# HoneyPI_Platine_2_0.net
KiCad netlist of a schematic drawn in EAGLE
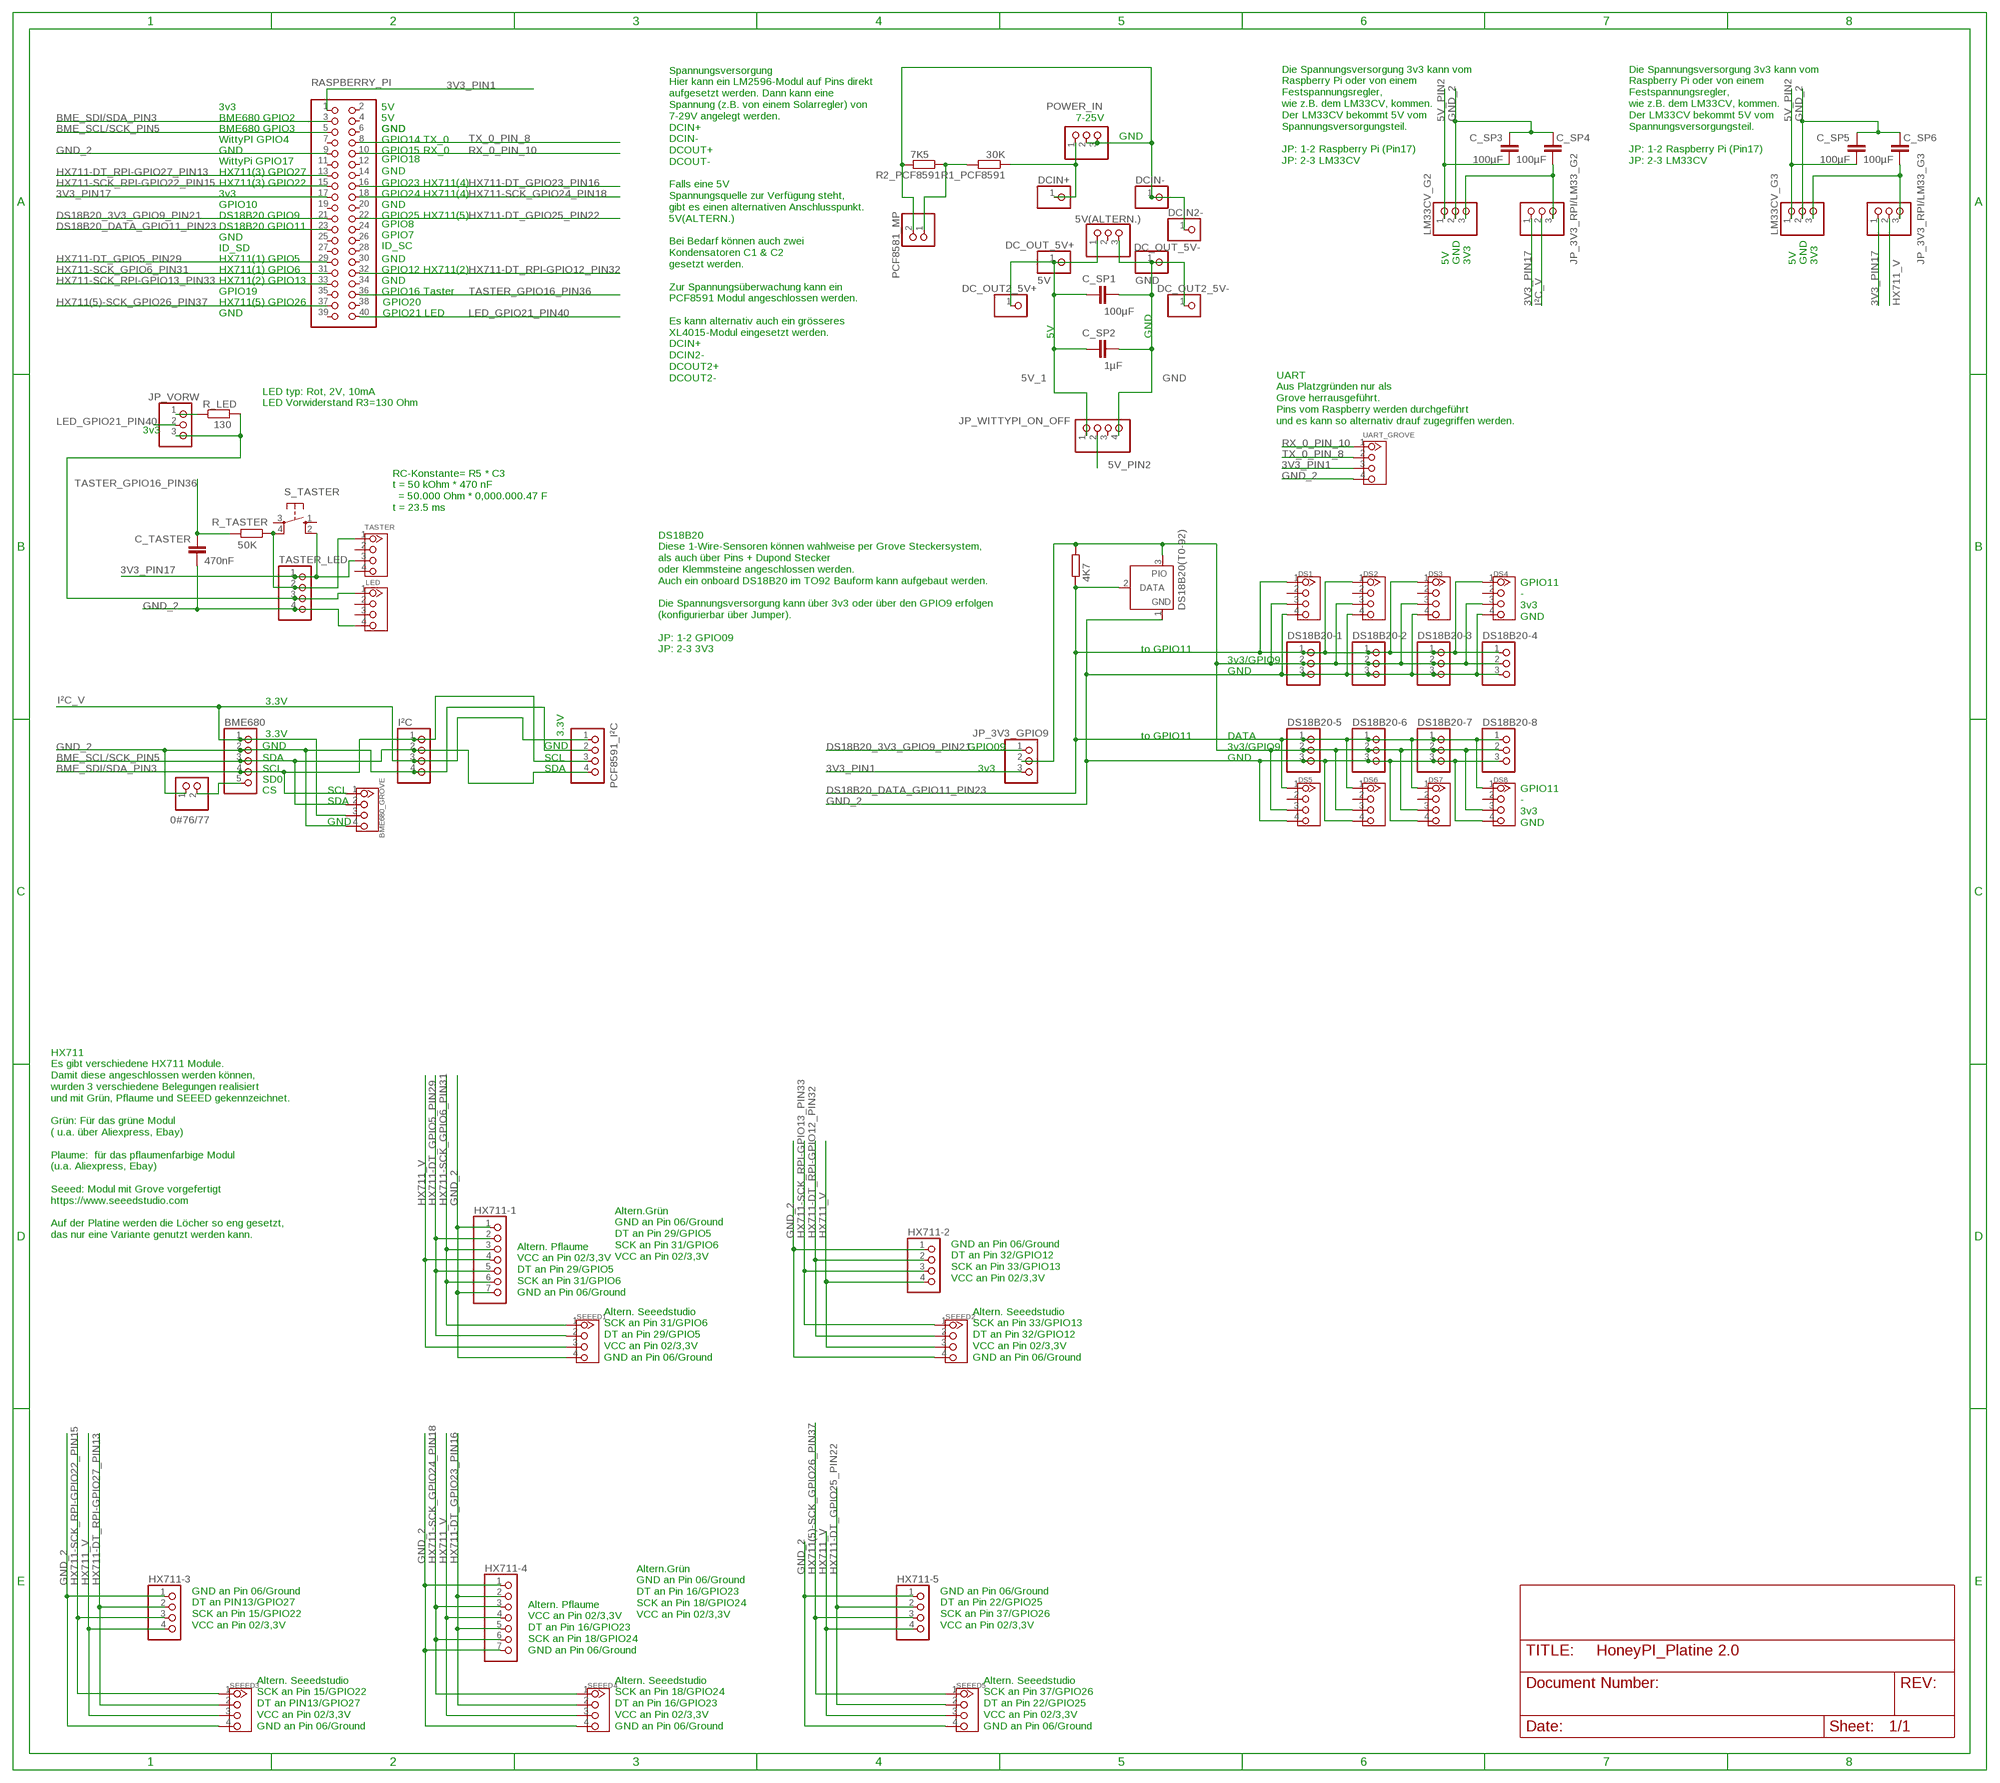
[diagram p0: schematic, sheet 1]

(export (version "E")
  (design (tool "Eeschema 10.0.6"))
  (components
    (comp (ref "0#76/77")
      (value "PINHD-1X2")
      (footprint "eagle-import:1X02")
      (libsource (lib "eagle-import") (part "PINHD-1X2"))
    )
    (comp (ref "5V(ALTERN.)")
      (value "PINHD-1X3")
      (footprint "eagle-import:1X03")
      (libsource (lib "eagle-import") (part "PINHD-1X3"))
    )
    (comp (ref "BME680")
      (value "PINHD-1X5")
      (footprint "eagle-import:1X05")
      (libsource (lib "eagle-import") (part "PINHD-1X5"))
    )
    (comp (ref "BME680_GROVE")
      (value "TWIG-4P-2.0-2.0")
      (footprint "eagle-import:4P-2.0")
      (libsource (lib "eagle-import") (part "TWIG-4P-2.0-2.0"))
    )
    (comp (ref "C_SP1")
      (value "100µF")
      (footprint "eagle-import:C2.5-3")
      (libsource (lib "eagle-import") (part "C2,5-3"))
    )
    (comp (ref "C_SP2")
      (value "1µF")
      (footprint "eagle-import:C2.5-3")
      (libsource (lib "eagle-import") (part "C2,5-3"))
    )
    (comp (ref "C_SP3")
      (value "100µF")
      (footprint "eagle-import:C2.5-3")
      (libsource (lib "eagle-import") (part "C2,5-3"))
    )
    (comp (ref "C_SP4")
      (value "100µF")
      (footprint "eagle-import:C2.5-3")
      (libsource (lib "eagle-import") (part "C2,5-3"))
    )
    (comp (ref "C_SP5")
      (value "100µF")
      (footprint "eagle-import:C2.5-3")
      (libsource (lib "eagle-import") (part "C2,5-3"))
    )
    (comp (ref "C_SP6")
      (value "100µF")
      (footprint "eagle-import:C2.5-3")
      (libsource (lib "eagle-import") (part "C2,5-3"))
    )
    (comp (ref "C_TASTER")
      (value "470nF")
      (footprint "eagle-import:C2.5-3")
      (libsource (lib "eagle-import") (part "C2,5-3"))
    )
    (comp (ref "DCIN+")
      (value "PINHD-1X1")
      (footprint "eagle-import:1X01")
      (libsource (lib "eagle-import") (part "PINHD-1X1"))
    )
    (comp (ref "DCIN-")
      (value "PINHD-1X1")
      (footprint "eagle-import:1X01")
      (libsource (lib "eagle-import") (part "PINHD-1X1"))
    )
    (comp (ref "DCIN2-")
      (value "PINHD-1X1")
      (footprint "eagle-import:1X01")
      (libsource (lib "eagle-import") (part "PINHD-1X1"))
    )
    (comp (ref "DC_OUT2_5V+")
      (value "PINHD-1X1")
      (footprint "eagle-import:1X01")
      (libsource (lib "eagle-import") (part "PINHD-1X1"))
    )
    (comp (ref "DC_OUT2_5V-")
      (value "PINHD-1X1")
      (footprint "eagle-import:1X01")
      (libsource (lib "eagle-import") (part "PINHD-1X1"))
    )
    (comp (ref "DC_OUT_5V+")
      (value "5V")
      (footprint "eagle-import:1X01")
      (libsource (lib "eagle-import") (part "PINHD-1X1"))
    )
    (comp (ref "DC_OUT_5V-")
      (value "GND")
      (footprint "eagle-import:1X01")
      (libsource (lib "eagle-import") (part "PINHD-1X1"))
    )
    (comp (ref "DS1")
      (value "TWIG-4P-2.0-2.0")
      (footprint "eagle-import:4P-2.0")
      (libsource (lib "eagle-import") (part "TWIG-4P-2.0-2.0"))
    )
    (comp (ref "DS2")
      (value "TWIG-4P-2.0-2.0")
      (footprint "eagle-import:4P-2.0")
      (libsource (lib "eagle-import") (part "TWIG-4P-2.0-2.0"))
    )
    (comp (ref "DS3")
      (value "TWIG-4P-2.0-2.0")
      (footprint "eagle-import:4P-2.0")
      (libsource (lib "eagle-import") (part "TWIG-4P-2.0-2.0"))
    )
    (comp (ref "DS4")
      (value "TWIG-4P-2.0-2.0")
      (footprint "eagle-import:4P-2.0")
      (libsource (lib "eagle-import") (part "TWIG-4P-2.0-2.0"))
    )
    (comp (ref "DS5")
      (value "TWIG-4P-2.0-2.0")
      (footprint "eagle-import:4P-2.0")
      (libsource (lib "eagle-import") (part "TWIG-4P-2.0-2.0"))
    )
    (comp (ref "DS6")
      (value "TWIG-4P-2.0-2.0")
      (footprint "eagle-import:4P-2.0")
      (libsource (lib "eagle-import") (part "TWIG-4P-2.0-2.0"))
    )
    (comp (ref "DS7")
      (value "TWIG-4P-2.0-2.0")
      (footprint "eagle-import:4P-2.0")
      (libsource (lib "eagle-import") (part "TWIG-4P-2.0-2.0"))
    )
    (comp (ref "DS8")
      (value "TWIG-4P-2.0-2.0")
      (footprint "eagle-import:4P-2.0")
      (libsource (lib "eagle-import") (part "TWIG-4P-2.0-2.0"))
    )
    (comp (ref "DS18B20(T0-92)")
      (value "DS18b20")
      (footprint "eagle-import:TO92-")
      (fields (field (name "MF") "DALLAS SEMICONDUCTOR") (field (name "MPN") "DS2405"))
      (libsource (lib "eagle-import") (part "DS2405"))
    )
    (comp (ref "DS18B20-1")
      (value "PINHD-1X3")
      (footprint "eagle-import:1X03")
      (libsource (lib "eagle-import") (part "PINHD-1X3"))
    )
    (comp (ref "DS18B20-2")
      (value "PINHD-1X3")
      (footprint "eagle-import:1X03")
      (libsource (lib "eagle-import") (part "PINHD-1X3"))
    )
    (comp (ref "DS18B20-3")
      (value "PINHD-1X3")
      (footprint "eagle-import:1X03")
      (libsource (lib "eagle-import") (part "PINHD-1X3"))
    )
    (comp (ref "DS18B20-4")
      (value "PINHD-1X3")
      (footprint "eagle-import:1X03")
      (libsource (lib "eagle-import") (part "PINHD-1X3"))
    )
    (comp (ref "DS18B20-5")
      (value "PINHD-1X3")
      (footprint "eagle-import:1X03")
      (libsource (lib "eagle-import") (part "PINHD-1X3"))
    )
    (comp (ref "DS18B20-6")
      (value "PINHD-1X3")
      (footprint "eagle-import:1X03")
      (libsource (lib "eagle-import") (part "PINHD-1X3"))
    )
    (comp (ref "DS18B20-7")
      (value "PINHD-1X3")
      (footprint "eagle-import:1X03")
      (libsource (lib "eagle-import") (part "PINHD-1X3"))
    )
    (comp (ref "DS18B20-8")
      (value "PINHD-1X3")
      (footprint "eagle-import:1X03")
      (libsource (lib "eagle-import") (part "PINHD-1X3"))
    )
    (comp (ref "HX711-1")
      (value "PINHD-1X7")
      (footprint "eagle-import:1X07")
      (libsource (lib "eagle-import") (part "PINHD-1X7"))
    )
    (comp (ref "HX711-2")
      (value "PINHD-1X4")
      (footprint "eagle-import:1X04")
      (libsource (lib "eagle-import") (part "PINHD-1X4"))
    )
    (comp (ref "HX711-3")
      (value "PINHD-1X4")
      (footprint "eagle-import:1X04")
      (libsource (lib "eagle-import") (part "PINHD-1X4"))
    )
    (comp (ref "HX711-4")
      (value "PINHD-1X7")
      (footprint "eagle-import:1X07")
      (libsource (lib "eagle-import") (part "PINHD-1X7"))
    )
    (comp (ref "HX711-5")
      (value "PINHD-1X4")
      (footprint "eagle-import:1X04")
      (libsource (lib "eagle-import") (part "PINHD-1X4"))
    )
    (comp (ref "I²C")
      (value "PINHD-1X4")
      (footprint "eagle-import:1X04")
      (libsource (lib "eagle-import") (part "PINHD-1X4"))
    )
    (comp (ref "JP_3V3_GPIO9")
      (value "PINHD-1X3")
      (footprint "eagle-import:1X03")
      (libsource (lib "eagle-import") (part "PINHD-1X3"))
    )
    (comp (ref "JP_3V3_RPI/LM33_G2")
      (value "PINHD-1X3")
      (footprint "eagle-import:1X03")
      (libsource (lib "eagle-import") (part "PINHD-1X3"))
    )
    (comp (ref "JP_3V3_RPI/LM33_G3")
      (value "PINHD-1X3")
      (footprint "eagle-import:1X03")
      (libsource (lib "eagle-import") (part "PINHD-1X3"))
    )
    (comp (ref "JP_VORW")
      (value "PINHD-1X3")
      (footprint "eagle-import:1X03")
      (libsource (lib "eagle-import") (part "PINHD-1X3"))
    )
    (comp (ref "JP_WITTYPI_ON_OFF")
      (value "PINHD-1X4")
      (footprint "eagle-import:1X04")
      (libsource (lib "eagle-import") (part "PINHD-1X4"))
    )
    (comp (ref "LED")
      (value "TWIG-4P-2.0-2.0")
      (footprint "eagle-import:4P-2.0")
      (libsource (lib "eagle-import") (part "TWIG-4P-2.0-2.0"))
    )
    (comp (ref "LM33CV_G2")
      (value "PINHD-1X3")
      (footprint "eagle-import:1X03")
      (libsource (lib "eagle-import") (part "PINHD-1X3"))
    )
    (comp (ref "LM33CV_G3")
      (value "PINHD-1X3")
      (footprint "eagle-import:1X03")
      (libsource (lib "eagle-import") (part "PINHD-1X3"))
    )
    (comp (ref "PCF8581_MP")
      (value "PINHD-1X2")
      (footprint "eagle-import:1X02")
      (libsource (lib "eagle-import") (part "PINHD-1X2"))
    )
    (comp (ref "PCF8591_I²C")
      (value "PINHD-1X4")
      (footprint "eagle-import:1X04")
      (libsource (lib "eagle-import") (part "PINHD-1X4"))
    )
    (comp (ref "POWER_IN")
      (value "PINHD-1X3")
      (footprint "eagle-import:1X03")
      (libsource (lib "eagle-import") (part "PINHD-1X3"))
    )
    (comp (ref "R1_PCF8591")
      (value "30K")
      (footprint "eagle-import:0204_7")
      (libsource (lib "eagle-import") (part "R-EU_0204/7"))
    )
    (comp (ref "R2_PCF8591")
      (value "7K5")
      (footprint "eagle-import:0204_7")
      (libsource (lib "eagle-import") (part "R-EU_0204/7"))
    )
    (comp (ref "RASPBERRY_PI")
      (value "PINHD-2X20")
      (footprint "eagle-import:2X20")
      (libsource (lib "eagle-import") (part "PINHD-2X20"))
    )
    (comp (ref "R_DS18B20")
      (value "4K7")
      (footprint "eagle-import:0204_7")
      (libsource (lib "eagle-import") (part "R-EU_0204/7"))
    )
    (comp (ref "R_LED")
      (value "130")
      (footprint "eagle-import:0204_7")
      (libsource (lib "eagle-import") (part "R-EU_0204/7"))
    )
    (comp (ref "R_TASTER")
      (value "50K")
      (footprint "eagle-import:0204_7")
      (libsource (lib "eagle-import") (part "R-EU_0204/7"))
    )
    (comp (ref "SEEED1")
      (value "TWIG-4P-2.0-2.0")
      (footprint "eagle-import:4P-2.0")
      (libsource (lib "eagle-import") (part "TWIG-4P-2.0-2.0"))
    )
    (comp (ref "SEEED2")
      (value "TWIG-4P-2.0-2.0")
      (footprint "eagle-import:4P-2.0")
      (libsource (lib "eagle-import") (part "TWIG-4P-2.0-2.0"))
    )
    (comp (ref "SEEED3")
      (value "TWIG-4P-2.0-2.0")
      (footprint "eagle-import:4P-2.0")
      (libsource (lib "eagle-import") (part "TWIG-4P-2.0-2.0"))
    )
    (comp (ref "SEEED4")
      (value "TWIG-4P-2.0-2.0")
      (footprint "eagle-import:4P-2.0")
      (libsource (lib "eagle-import") (part "TWIG-4P-2.0-2.0"))
    )
    (comp (ref "SEEED5")
      (value "TWIG-4P-2.0-2.0")
      (footprint "eagle-import:4P-2.0")
      (libsource (lib "eagle-import") (part "TWIG-4P-2.0-2.0"))
    )
    (comp (ref "S_TASTER")
      (value "10-XX")
      (footprint "eagle-import:B3F-10XX")
      (fields (field (name "MPN") "B3F-1000"))
      (libsource (lib "eagle-import") (part "10-XX"))
    )
    (comp (ref "TASTER")
      (value "TWIG-4P-2.0-2.0")
      (footprint "eagle-import:4P-2.0")
      (libsource (lib "eagle-import") (part "TWIG-4P-2.0-2.0"))
    )
    (comp (ref "TASTER_LED")
      (value "PINHD-1X4")
      (footprint "eagle-import:1X04")
      (libsource (lib "eagle-import") (part "PINHD-1X4"))
    )
    (comp (ref "UART_GROVE")
      (value "TWIG-4P-2.0-2.0")
      (footprint "eagle-import:4P-2.0")
      (libsource (lib "eagle-import") (part "TWIG-4P-2.0-2.0"))
    )
  )
  (nets
    (net (code "1") (name "/3V3_PIN1") (class "Default")
      (node (ref "JP_3V3_GPIO9") (pin "3") (pinfunction "3_3") (pintype "passive"))
      (node (ref "RASPBERRY_PI") (pin "1") (pinfunction "1_1") (pintype "passive"))
      (node (ref "UART_GROVE") (pin "3") (pinfunction "3_3") (pintype "bidirectional"))
    )
    (net (code "2") (name "/3V3_PIN17") (class "Default")
      (node (ref "JP_3V3_RPI/LM33_G2") (pin "1") (pinfunction "1_1") (pintype "passive"))
      (node (ref "JP_3V3_RPI/LM33_G3") (pin "1") (pinfunction "1_1") (pintype "passive"))
      (node (ref "RASPBERRY_PI") (pin "17") (pinfunction "17_17") (pintype "passive"))
      (node (ref "S_TASTER") (pin "2") (pinfunction "S1_2") (pintype "passive"))
      (node (ref "TASTER") (pin "3") (pinfunction "3_3") (pintype "bidirectional"))
      (node (ref "TASTER_LED") (pin "1") (pinfunction "1_1") (pintype "passive"))
    )
    (net (code "3") (name "/5V_1") (class "Default")
      (node (ref "5V(ALTERN.)") (pin "1") (pinfunction "1_1") (pintype "passive"))
      (node (ref "C_SP1") (pin "1") (pinfunction "1_1") (pintype "passive"))
      (node (ref "C_SP2") (pin "1") (pinfunction "1_1") (pintype "passive"))
      (node (ref "DC_OUT2_5V+") (pin "1") (pinfunction "1_1") (pintype "passive"))
      (node (ref "DC_OUT_5V+") (pin "1") (pinfunction "1_1") (pintype "passive"))
      (node (ref "JP_WITTYPI_ON_OFF") (pin "1") (pinfunction "1_1") (pintype "passive"))
    )
    (net (code "4") (name "/5V_PIN2") (class "Default")
      (node (ref "C_SP3") (pin "1") (pinfunction "1_1") (pintype "passive"))
      (node (ref "C_SP5") (pin "1") (pinfunction "1_1") (pintype "passive"))
      (node (ref "JP_WITTYPI_ON_OFF") (pin "2") (pinfunction "2_2") (pintype "passive"))
      (node (ref "LM33CV_G2") (pin "1") (pinfunction "1_1") (pintype "passive"))
      (node (ref "LM33CV_G3") (pin "1") (pinfunction "1_1") (pintype "passive"))
    )
    (net (code "5") (name "/BME_SCL{slash}SCK_PIN5") (class "Default")
      (node (ref "BME680") (pin "3") (pinfunction "3_3") (pintype "passive"))
      (node (ref "BME680_GROVE") (pin "2") (pinfunction "2_2") (pintype "bidirectional"))
      (node (ref "I²C") (pin "2") (pinfunction "2_2") (pintype "passive"))
      (node (ref "PCF8591_I²C") (pin "4") (pinfunction "4_4") (pintype "passive"))
      (node (ref "RASPBERRY_PI") (pin "5") (pinfunction "5_5") (pintype "passive"))
    )
    (net (code "6") (name "/BME_SDI{slash}SDA_PIN3") (class "Default")
      (node (ref "BME680") (pin "4") (pinfunction "4_4") (pintype "passive"))
      (node (ref "BME680_GROVE") (pin "1") (pinfunction "1_1") (pintype "bidirectional"))
      (node (ref "I²C") (pin "1") (pinfunction "1_1") (pintype "passive"))
      (node (ref "PCF8591_I²C") (pin "3") (pinfunction "3_3") (pintype "passive"))
      (node (ref "RASPBERRY_PI") (pin "3") (pinfunction "3_3") (pintype "passive"))
    )
    (net (code "7") (name "/DS18B20_3V3_GPIO9_PIN21") (class "Default")
      (node (ref "JP_3V3_GPIO9") (pin "1") (pinfunction "1_1") (pintype "passive"))
      (node (ref "RASPBERRY_PI") (pin "21") (pinfunction "21_21") (pintype "passive"))
    )
    (net (code "8") (name "/DS18B20_DATA_GPIO11_PIN23") (class "Default")
      (node (ref "DS1") (pin "1") (pinfunction "1_1") (pintype "bidirectional"))
      (node (ref "DS18B20(T0-92)") (pin "2") (pinfunction "DATA_2") (pintype "input"))
      (node (ref "DS18B20-1") (pin "1") (pinfunction "1_1") (pintype "passive"))
      (node (ref "DS18B20-2") (pin "1") (pinfunction "1_1") (pintype "passive"))
      (node (ref "DS18B20-3") (pin "1") (pinfunction "1_1") (pintype "passive"))
      (node (ref "DS18B20-4") (pin "1") (pinfunction "1_1") (pintype "passive"))
      (node (ref "DS18B20-5") (pin "1") (pinfunction "1_1") (pintype "passive"))
      (node (ref "DS18B20-6") (pin "1") (pinfunction "1_1") (pintype "passive"))
      (node (ref "DS18B20-7") (pin "1") (pinfunction "1_1") (pintype "passive"))
      (node (ref "DS18B20-8") (pin "1") (pinfunction "1_1") (pintype "passive"))
      (node (ref "DS2") (pin "1") (pinfunction "1_1") (pintype "bidirectional"))
      (node (ref "DS3") (pin "1") (pinfunction "1_1") (pintype "bidirectional"))
      (node (ref "DS4") (pin "1") (pinfunction "1_1") (pintype "bidirectional"))
      (node (ref "DS5") (pin "1") (pinfunction "1_1") (pintype "bidirectional"))
      (node (ref "DS6") (pin "1") (pinfunction "1_1") (pintype "bidirectional"))
      (node (ref "DS7") (pin "1") (pinfunction "1_1") (pintype "bidirectional"))
      (node (ref "DS8") (pin "1") (pinfunction "1_1") (pintype "bidirectional"))
      (node (ref "RASPBERRY_PI") (pin "23") (pinfunction "23_23") (pintype "passive"))
      (node (ref "R_DS18B20") (pin "1") (pinfunction "1_1") (pintype "passive"))
    )
    (net (code "9") (name "/GND") (class "Default")
      (node (ref "5V(ALTERN.)") (pin "3") (pinfunction "3_3") (pintype "passive"))
      (node (ref "C_SP1") (pin "2") (pinfunction "2_2") (pintype "passive"))
      (node (ref "C_SP2") (pin "2") (pinfunction "2_2") (pintype "passive"))
      (node (ref "DC_OUT2_5V-") (pin "1") (pinfunction "1_1") (pintype "passive"))
      (node (ref "DC_OUT_5V-") (pin "1") (pinfunction "1_1") (pintype "passive"))
      (node (ref "JP_WITTYPI_ON_OFF") (pin "4") (pinfunction "4_4") (pintype "passive"))
    )
    (net (code "10") (name "/GND_2") (class "Default")
      (node (ref "0#76/77") (pin "1") (pinfunction "1_1") (pintype "passive"))
      (node (ref "BME680") (pin "2") (pinfunction "2_2") (pintype "passive"))
      (node (ref "BME680_GROVE") (pin "4") (pinfunction "4_4") (pintype "bidirectional"))
      (node (ref "C_SP3") (pin "2") (pinfunction "2_2") (pintype "passive"))
      (node (ref "C_SP4") (pin "2") (pinfunction "2_2") (pintype "passive"))
      (node (ref "C_SP5") (pin "2") (pinfunction "2_2") (pintype "passive"))
      (node (ref "C_SP6") (pin "2") (pinfunction "2_2") (pintype "passive"))
      (node (ref "C_TASTER") (pin "1") (pinfunction "1_1") (pintype "passive"))
      (node (ref "DS1") (pin "4") (pinfunction "4_4") (pintype "bidirectional"))
      (node (ref "DS18B20(T0-92)") (pin "1") (pinfunction "GND_1") (pintype "passive"))
      (node (ref "DS18B20-1") (pin "3") (pinfunction "3_3") (pintype "passive"))
      (node (ref "DS18B20-2") (pin "3") (pinfunction "3_3") (pintype "passive"))
      (node (ref "DS18B20-3") (pin "3") (pinfunction "3_3") (pintype "passive"))
      (node (ref "DS18B20-4") (pin "3") (pinfunction "3_3") (pintype "passive"))
      (node (ref "DS18B20-5") (pin "3") (pinfunction "3_3") (pintype "passive"))
      (node (ref "DS18B20-6") (pin "3") (pinfunction "3_3") (pintype "passive"))
      (node (ref "DS18B20-7") (pin "3") (pinfunction "3_3") (pintype "passive"))
      (node (ref "DS18B20-8") (pin "3") (pinfunction "3_3") (pintype "passive"))
      (node (ref "DS2") (pin "4") (pinfunction "4_4") (pintype "bidirectional"))
      (node (ref "DS3") (pin "4") (pinfunction "4_4") (pintype "bidirectional"))
      (node (ref "DS4") (pin "4") (pinfunction "4_4") (pintype "bidirectional"))
      (node (ref "DS5") (pin "4") (pinfunction "4_4") (pintype "bidirectional"))
      (node (ref "DS6") (pin "4") (pinfunction "4_4") (pintype "bidirectional"))
      (node (ref "DS7") (pin "4") (pinfunction "4_4") (pintype "bidirectional"))
      (node (ref "DS8") (pin "4") (pinfunction "4_4") (pintype "bidirectional"))
      (node (ref "HX711-1") (pin "1") (pinfunction "1_1") (pintype "passive"))
      (node (ref "HX711-1") (pin "7") (pinfunction "7_7") (pintype "passive"))
      (node (ref "HX711-2") (pin "1") (pinfunction "1_1") (pintype "passive"))
      (node (ref "HX711-3") (pin "1") (pinfunction "1_1") (pintype "passive"))
      (node (ref "HX711-4") (pin "1") (pinfunction "1_1") (pintype "passive"))
      (node (ref "HX711-4") (pin "7") (pinfunction "7_7") (pintype "passive"))
      (node (ref "HX711-5") (pin "1") (pinfunction "1_1") (pintype "passive"))
      (node (ref "I²C") (pin "4") (pinfunction "4_4") (pintype "passive"))
      (node (ref "LED") (pin "4") (pinfunction "4_4") (pintype "bidirectional"))
      (node (ref "LM33CV_G2") (pin "2") (pinfunction "2_2") (pintype "passive"))
      (node (ref "LM33CV_G3") (pin "2") (pinfunction "2_2") (pintype "passive"))
      (node (ref "PCF8591_I²C") (pin "2") (pinfunction "2_2") (pintype "passive"))
      (node (ref "RASPBERRY_PI") (pin "9") (pinfunction "9_9") (pintype "passive"))
      (node (ref "SEEED1") (pin "4") (pinfunction "4_4") (pintype "bidirectional"))
      (node (ref "SEEED2") (pin "4") (pinfunction "4_4") (pintype "bidirectional"))
      (node (ref "SEEED3") (pin "4") (pinfunction "4_4") (pintype "bidirectional"))
      (node (ref "SEEED4") (pin "4") (pinfunction "4_4") (pintype "bidirectional"))
      (node (ref "SEEED5") (pin "4") (pinfunction "4_4") (pintype "bidirectional"))
      (node (ref "TASTER_LED") (pin "4") (pinfunction "4_4") (pintype "passive"))
      (node (ref "UART_GROVE") (pin "4") (pinfunction "4_4") (pintype "bidirectional"))
    )
    (net (code "11") (name "/HX711(5)-SCK_GPIO26_PIN37") (class "Default")
      (node (ref "HX711-5") (pin "3") (pinfunction "3_3") (pintype "passive"))
      (node (ref "RASPBERRY_PI") (pin "37") (pinfunction "37_37") (pintype "passive"))
      (node (ref "SEEED5") (pin "1") (pinfunction "1_1") (pintype "bidirectional"))
    )
    (net (code "12") (name "/HX711-DT_GPIO5_PIN29") (class "Default")
      (node (ref "HX711-1") (pin "2") (pinfunction "2_2") (pintype "passive"))
      (node (ref "HX711-1") (pin "5") (pinfunction "5_5") (pintype "passive"))
      (node (ref "RASPBERRY_PI") (pin "29") (pinfunction "29_29") (pintype "passive"))
      (node (ref "SEEED1") (pin "2") (pinfunction "2_2") (pintype "bidirectional"))
    )
    (net (code "13") (name "/HX711-DT_GPIO23_PIN16") (class "Default")
      (node (ref "HX711-4") (pin "2") (pinfunction "2_2") (pintype "passive"))
      (node (ref "HX711-4") (pin "5") (pinfunction "5_5") (pintype "passive"))
      (node (ref "RASPBERRY_PI") (pin "16") (pinfunction "16_16") (pintype "passive"))
      (node (ref "SEEED4") (pin "2") (pinfunction "2_2") (pintype "bidirectional"))
    )
    (net (code "14") (name "/HX711-DT_GPIO25_PIN22") (class "Default")
      (node (ref "HX711-5") (pin "2") (pinfunction "2_2") (pintype "passive"))
      (node (ref "RASPBERRY_PI") (pin "22") (pinfunction "22_22") (pintype "passive"))
      (node (ref "SEEED5") (pin "2") (pinfunction "2_2") (pintype "bidirectional"))
    )
    (net (code "15") (name "/HX711-DT_RPI-GPIO12_PIN32") (class "Default")
      (node (ref "HX711-2") (pin "2") (pinfunction "2_2") (pintype "passive"))
      (node (ref "RASPBERRY_PI") (pin "32") (pinfunction "32_32") (pintype "passive"))
      (node (ref "SEEED2") (pin "2") (pinfunction "2_2") (pintype "bidirectional"))
    )
    (net (code "16") (name "/HX711-DT_RPI-GPIO27_PIN13") (class "Default")
      (node (ref "HX711-3") (pin "2") (pinfunction "2_2") (pintype "passive"))
      (node (ref "RASPBERRY_PI") (pin "13") (pinfunction "13_13") (pintype "passive"))
      (node (ref "SEEED3") (pin "2") (pinfunction "2_2") (pintype "bidirectional"))
    )
    (net (code "17") (name "/HX711-SCK_GPIO6_PIN31") (class "Default")
      (node (ref "HX711-1") (pin "3") (pinfunction "3_3") (pintype "passive"))
      (node (ref "HX711-1") (pin "6") (pinfunction "6_6") (pintype "passive"))
      (node (ref "RASPBERRY_PI") (pin "31") (pinfunction "31_31") (pintype "passive"))
      (node (ref "SEEED1") (pin "1") (pinfunction "1_1") (pintype "bidirectional"))
    )
    (net (code "18") (name "/HX711-SCK_GPIO24_PIN18") (class "Default")
      (node (ref "HX711-4") (pin "3") (pinfunction "3_3") (pintype "passive"))
      (node (ref "HX711-4") (pin "6") (pinfunction "6_6") (pintype "passive"))
      (node (ref "RASPBERRY_PI") (pin "18") (pinfunction "18_18") (pintype "passive"))
      (node (ref "SEEED4") (pin "1") (pinfunction "1_1") (pintype "bidirectional"))
    )
    (net (code "19") (name "/HX711-SCK_RPI-GPIO13_PIN33") (class "Default")
      (node (ref "HX711-2") (pin "3") (pinfunction "3_3") (pintype "passive"))
      (node (ref "RASPBERRY_PI") (pin "33") (pinfunction "33_33") (pintype "passive"))
      (node (ref "SEEED2") (pin "1") (pinfunction "1_1") (pintype "bidirectional"))
    )
    (net (code "20") (name "/HX711-SCK_RPI-GPIO22_PIN15") (class "Default")
      (node (ref "HX711-3") (pin "3") (pinfunction "3_3") (pintype "passive"))
      (node (ref "RASPBERRY_PI") (pin "15") (pinfunction "15_15") (pintype "passive"))
      (node (ref "SEEED3") (pin "1") (pinfunction "1_1") (pintype "bidirectional"))
    )
    (net (code "21") (name "/HX711_V") (class "Default")
      (node (ref "HX711-1") (pin "4") (pinfunction "4_4") (pintype "passive"))
      (node (ref "HX711-2") (pin "4") (pinfunction "4_4") (pintype "passive"))
      (node (ref "HX711-3") (pin "4") (pinfunction "4_4") (pintype "passive"))
      (node (ref "HX711-4") (pin "4") (pinfunction "4_4") (pintype "passive"))
      (node (ref "HX711-5") (pin "4") (pinfunction "4_4") (pintype "passive"))
      (node (ref "JP_3V3_RPI/LM33_G3") (pin "2") (pinfunction "2_2") (pintype "passive"))
      (node (ref "SEEED1") (pin "3") (pinfunction "3_3") (pintype "bidirectional"))
      (node (ref "SEEED2") (pin "3") (pinfunction "3_3") (pintype "bidirectional"))
      (node (ref "SEEED3") (pin "3") (pinfunction "3_3") (pintype "bidirectional"))
      (node (ref "SEEED4") (pin "3") (pinfunction "3_3") (pintype "bidirectional"))
      (node (ref "SEEED5") (pin "3") (pinfunction "3_3") (pintype "bidirectional"))
    )
    (net (code "22") (name "/I²C_V") (class "Default")
      (node (ref "BME680") (pin "1") (pinfunction "1_1") (pintype "passive"))
      (node (ref "BME680_GROVE") (pin "3") (pinfunction "3_3") (pintype "bidirectional"))
      (node (ref "I²C") (pin "3") (pinfunction "3_3") (pintype "passive"))
      (node (ref "JP_3V3_RPI/LM33_G2") (pin "2") (pinfunction "2_2") (pintype "passive"))
      (node (ref "PCF8591_I²C") (pin "1") (pinfunction "1_1") (pintype "passive"))
    )
    (net (code "23") (name "/LED_GPIO21_PIN40") (class "Default")
      (node (ref "JP_VORW") (pin "2") (pinfunction "2_2") (pintype "passive"))
      (node (ref "RASPBERRY_PI") (pin "40") (pinfunction "40_40") (pintype "passive"))
    )
    (net (code "24") (name "/RX_0_PIN_10") (class "Default")
      (node (ref "RASPBERRY_PI") (pin "10") (pinfunction "10_10") (pintype "passive"))
      (node (ref "UART_GROVE") (pin "1") (pinfunction "1_1") (pintype "bidirectional"))
    )
    (net (code "25") (name "/TASTER_GPIO16_PIN36") (class "Default")
      (node (ref "C_TASTER") (pin "2") (pinfunction "2_2") (pintype "passive"))
      (node (ref "RASPBERRY_PI") (pin "36") (pinfunction "36_36") (pintype "passive"))
      (node (ref "R_TASTER") (pin "2") (pinfunction "2_2") (pintype "passive"))
    )
    (net (code "26") (name "/TX_0_PIN_8") (class "Default")
      (node (ref "RASPBERRY_PI") (pin "8") (pinfunction "8_8") (pintype "passive"))
      (node (ref "UART_GROVE") (pin "2") (pinfunction "2_2") (pintype "bidirectional"))
    )
    (net (code "27") (name "Net-(0#76/77-Pad2)") (class "Default")
      (node (ref "0#76/77") (pin "2") (pinfunction "2_2") (pintype "passive"))
      (node (ref "BME680") (pin "5") (pinfunction "5_5") (pintype "passive"))
    )
    (net (code "28") (name "Net-(C_SP4-Pad1)") (class "Default")
      (node (ref "C_SP4") (pin "1") (pinfunction "1_1") (pintype "passive"))
      (node (ref "JP_3V3_RPI/LM33_G2") (pin "3") (pinfunction "3_3") (pintype "passive"))
      (node (ref "LM33CV_G2") (pin "3") (pinfunction "3_3") (pintype "passive"))
    )
    (net (code "29") (name "Net-(C_SP6-Pad1)") (class "Default")
      (node (ref "C_SP6") (pin "1") (pinfunction "1_1") (pintype "passive"))
      (node (ref "JP_3V3_RPI/LM33_G3") (pin "3") (pinfunction "3_3") (pintype "passive"))
      (node (ref "LM33CV_G3") (pin "3") (pinfunction "3_3") (pintype "passive"))
    )
    (net (code "30") (name "Net-(DCIN+-Pad1)") (class "Default")
      (node (ref "DCIN+") (pin "1") (pinfunction "1_1") (pintype "passive"))
      (node (ref "POWER_IN") (pin "1") (pinfunction "1_1") (pintype "passive"))
      (node (ref "R1_PCF8591") (pin "1") (pinfunction "1_1") (pintype "passive"))
    )
    (net (code "31") (name "Net-(DCIN--Pad1)") (class "Default")
      (node (ref "DCIN-") (pin "1") (pinfunction "1_1") (pintype "passive"))
      (node (ref "DCIN2-") (pin "1") (pinfunction "1_1") (pintype "passive"))
      (node (ref "PCF8581_MP") (pin "2") (pinfunction "2_2") (pintype "passive"))
      (node (ref "POWER_IN") (pin "2") (pinfunction "2_2") (pintype "passive"))
      (node (ref "POWER_IN") (pin "3") (pinfunction "3_3") (pintype "passive"))
      (node (ref "R2_PCF8591") (pin "2") (pinfunction "2_2") (pintype "passive"))
    )
    (net (code "32") (name "Net-(DS18B20(T0-92)-PIO)") (class "Default")
      (node (ref "DS1") (pin "3") (pinfunction "3_3") (pintype "bidirectional"))
      (node (ref "DS18B20(T0-92)") (pin "3") (pinfunction "PIO_3") (pintype "passive"))
      (node (ref "DS18B20-1") (pin "2") (pinfunction "2_2") (pintype "passive"))
      (node (ref "DS18B20-2") (pin "2") (pinfunction "2_2") (pintype "passive"))
      (node (ref "DS18B20-3") (pin "2") (pinfunction "2_2") (pintype "passive"))
      (node (ref "DS18B20-4") (pin "2") (pinfunction "2_2") (pintype "passive"))
      (node (ref "DS18B20-5") (pin "2") (pinfunction "2_2") (pintype "passive"))
      (node (ref "DS18B20-6") (pin "2") (pinfunction "2_2") (pintype "passive"))
      (node (ref "DS18B20-7") (pin "2") (pinfunction "2_2") (pintype "passive"))
      (node (ref "DS18B20-8") (pin "2") (pinfunction "2_2") (pintype "passive"))
      (node (ref "DS2") (pin "3") (pinfunction "3_3") (pintype "bidirectional"))
      (node (ref "DS3") (pin "3") (pinfunction "3_3") (pintype "bidirectional"))
      (node (ref "DS4") (pin "3") (pinfunction "3_3") (pintype "bidirectional"))
      (node (ref "DS5") (pin "3") (pinfunction "3_3") (pintype "bidirectional"))
      (node (ref "DS6") (pin "3") (pinfunction "3_3") (pintype "bidirectional"))
      (node (ref "DS7") (pin "3") (pinfunction "3_3") (pintype "bidirectional"))
      (node (ref "DS8") (pin "3") (pinfunction "3_3") (pintype "bidirectional"))
      (node (ref "JP_3V3_GPIO9") (pin "2") (pinfunction "2_2") (pintype "passive"))
      (node (ref "R_DS18B20") (pin "2") (pinfunction "2_2") (pintype "passive"))
    )
    (net (code "33") (name "Net-(JP_VORW-Pad1)") (class "Default")
      (node (ref "JP_VORW") (pin "1") (pinfunction "1_1") (pintype "passive"))
      (node (ref "R_LED") (pin "1") (pinfunction "1_1") (pintype "passive"))
    )
    (net (code "34") (name "Net-(JP_VORW-Pad3)") (class "Default")
      (node (ref "JP_VORW") (pin "3") (pinfunction "3_3") (pintype "passive"))
      (node (ref "LED") (pin "1") (pinfunction "1_1") (pintype "bidirectional"))
      (node (ref "R_LED") (pin "2") (pinfunction "2_2") (pintype "passive"))
      (node (ref "TASTER_LED") (pin "3") (pinfunction "3_3") (pintype "passive"))
    )
    (net (code "35") (name "Net-(PCF8581_MP-Pad1)") (class "Default")
      (node (ref "PCF8581_MP") (pin "1") (pinfunction "1_1") (pintype "passive"))
      (node (ref "R1_PCF8591") (pin "2") (pinfunction "2_2") (pintype "passive"))
      (node (ref "R2_PCF8591") (pin "1") (pinfunction "1_1") (pintype "passive"))
    )
    (net (code "36") (name "Net-(S_TASTER-P1)") (class "Default")
      (node (ref "R_TASTER") (pin "1") (pinfunction "1_1") (pintype "passive"))
      (node (ref "S_TASTER") (pin "4") (pinfunction "P1_4") (pintype "passive"))
      (node (ref "TASTER") (pin "1") (pinfunction "1_1") (pintype "bidirectional"))
      (node (ref "TASTER_LED") (pin "2") (pinfunction "2_2") (pintype "passive"))
    )
    (net (code "37") (name "unconnected-(5V(ALTERN.)-Pad2)") (class "Default")
      (node (ref "5V(ALTERN.)") (pin "2") (pinfunction "2_2") (pintype "passive"))
    )
    (net (code "38") (name "unconnected-(DS1-Pad2)") (class "Default")
      (node (ref "DS1") (pin "2") (pinfunction "2_2") (pintype "bidirectional"))
    )
    (net (code "39") (name "unconnected-(DS2-Pad2)") (class "Default")
      (node (ref "DS2") (pin "2") (pinfunction "2_2") (pintype "bidirectional"))
    )
    (net (code "40") (name "unconnected-(DS3-Pad2)") (class "Default")
      (node (ref "DS3") (pin "2") (pinfunction "2_2") (pintype "bidirectional"))
    )
    (net (code "41") (name "unconnected-(DS4-Pad2)") (class "Default")
      (node (ref "DS4") (pin "2") (pinfunction "2_2") (pintype "bidirectional"))
    )
    (net (code "42") (name "unconnected-(DS5-Pad2)") (class "Default")
      (node (ref "DS5") (pin "2") (pinfunction "2_2") (pintype "bidirectional"))
    )
    (net (code "43") (name "unconnected-(DS6-Pad2)") (class "Default")
      (node (ref "DS6") (pin "2") (pinfunction "2_2") (pintype "bidirectional"))
    )
    (net (code "44") (name "unconnected-(DS7-Pad2)") (class "Default")
      (node (ref "DS7") (pin "2") (pinfunction "2_2") (pintype "bidirectional"))
    )
    (net (code "45") (name "unconnected-(DS8-Pad2)") (class "Default")
      (node (ref "DS8") (pin "2") (pinfunction "2_2") (pintype "bidirectional"))
    )
    (net (code "46") (name "unconnected-(JP_WITTYPI_ON_OFF-Pad3)") (class "Default")
      (node (ref "JP_WITTYPI_ON_OFF") (pin "3") (pinfunction "3_3") (pintype "passive"))
    )
    (net (code "47") (name "unconnected-(LED-Pad2)") (class "Default")
      (node (ref "LED") (pin "2") (pinfunction "2_2") (pintype "bidirectional"))
    )
    (net (code "48") (name "unconnected-(LED-Pad3)") (class "Default")
      (node (ref "LED") (pin "3") (pinfunction "3_3") (pintype "bidirectional"))
    )
    (net (code "49") (name "unconnected-(RASPBERRY_PI-Pad2)") (class "Default")
      (node (ref "RASPBERRY_PI") (pin "2") (pinfunction "2_2") (pintype "passive"))
    )
    (net (code "50") (name "unconnected-(RASPBERRY_PI-Pad4)") (class "Default")
      (node (ref "RASPBERRY_PI") (pin "4") (pinfunction "4_4") (pintype "passive"))
    )
    (net (code "51") (name "unconnected-(RASPBERRY_PI-Pad6)") (class "Default")
      (node (ref "RASPBERRY_PI") (pin "6") (pinfunction "6_6") (pintype "passive"))
    )
    (net (code "52") (name "unconnected-(RASPBERRY_PI-Pad7)") (class "Default")
      (node (ref "RASPBERRY_PI") (pin "7") (pinfunction "7_7") (pintype "passive"))
    )
    (net (code "53") (name "unconnected-(RASPBERRY_PI-Pad11)") (class "Default")
      (node (ref "RASPBERRY_PI") (pin "11") (pinfunction "11_11") (pintype "passive"))
    )
    (net (code "54") (name "unconnected-(RASPBERRY_PI-Pad12)") (class "Default")
      (node (ref "RASPBERRY_PI") (pin "12") (pinfunction "12_12") (pintype "passive"))
    )
    (net (code "55") (name "unconnected-(RASPBERRY_PI-Pad14)") (class "Default")
      (node (ref "RASPBERRY_PI") (pin "14") (pinfunction "14_14") (pintype "passive"))
    )
    (net (code "56") (name "unconnected-(RASPBERRY_PI-Pad19)") (class "Default")
      (node (ref "RASPBERRY_PI") (pin "19") (pinfunction "19_19") (pintype "passive"))
    )
    (net (code "57") (name "unconnected-(RASPBERRY_PI-Pad20)") (class "Default")
      (node (ref "RASPBERRY_PI") (pin "20") (pinfunction "20_20") (pintype "passive"))
    )
    (net (code "58") (name "unconnected-(RASPBERRY_PI-Pad24)") (class "Default")
      (node (ref "RASPBERRY_PI") (pin "24") (pinfunction "24_24") (pintype "passive"))
    )
    (net (code "59") (name "unconnected-(RASPBERRY_PI-Pad25)") (class "Default")
      (node (ref "RASPBERRY_PI") (pin "25") (pinfunction "25_25") (pintype "passive"))
    )
    (net (code "60") (name "unconnected-(RASPBERRY_PI-Pad26)") (class "Default")
      (node (ref "RASPBERRY_PI") (pin "26") (pinfunction "26_26") (pintype "passive"))
    )
    (net (code "61") (name "unconnected-(RASPBERRY_PI-Pad27)") (class "Default")
      (node (ref "RASPBERRY_PI") (pin "27") (pinfunction "27_27") (pintype "passive"))
    )
    (net (code "62") (name "unconnected-(RASPBERRY_PI-Pad28)") (class "Default")
      (node (ref "RASPBERRY_PI") (pin "28") (pinfunction "28_28") (pintype "passive"))
    )
    (net (code "63") (name "unconnected-(RASPBERRY_PI-Pad30)") (class "Default")
      (node (ref "RASPBERRY_PI") (pin "30") (pinfunction "30_30") (pintype "passive"))
    )
    (net (code "64") (name "unconnected-(RASPBERRY_PI-Pad34)") (class "Default")
      (node (ref "RASPBERRY_PI") (pin "34") (pinfunction "34_34") (pintype "passive"))
    )
    (net (code "65") (name "unconnected-(RASPBERRY_PI-Pad35)") (class "Default")
      (node (ref "RASPBERRY_PI") (pin "35") (pinfunction "35_35") (pintype "passive"))
    )
    (net (code "66") (name "unconnected-(RASPBERRY_PI-Pad38)") (class "Default")
      (node (ref "RASPBERRY_PI") (pin "38") (pinfunction "38_38") (pintype "passive"))
    )
    (net (code "67") (name "unconnected-(RASPBERRY_PI-Pad39)") (class "Default")
      (node (ref "RASPBERRY_PI") (pin "39") (pinfunction "39_39") (pintype "passive"))
    )
    (net (code "68") (name "unconnected-(S_TASTER-P-Pad3)") (class "Default")
      (node (ref "S_TASTER") (pin "3") (pinfunction "P_3") (pintype "passive"))
    )
    (net (code "69") (name "unconnected-(S_TASTER-S-Pad1)") (class "Default")
      (node (ref "S_TASTER") (pin "1") (pinfunction "S_1") (pintype "passive"))
    )
    (net (code "70") (name "unconnected-(TASTER-Pad2)") (class "Default")
      (node (ref "TASTER") (pin "2") (pinfunction "2_2") (pintype "bidirectional"))
    )
    (net (code "71") (name "unconnected-(TASTER-Pad4)") (class "Default")
      (node (ref "TASTER") (pin "4") (pinfunction "4_4") (pintype "bidirectional"))
    )
  )
)
